# STM32.net
KiCad netlist of a schematic drawn in Altium Designer
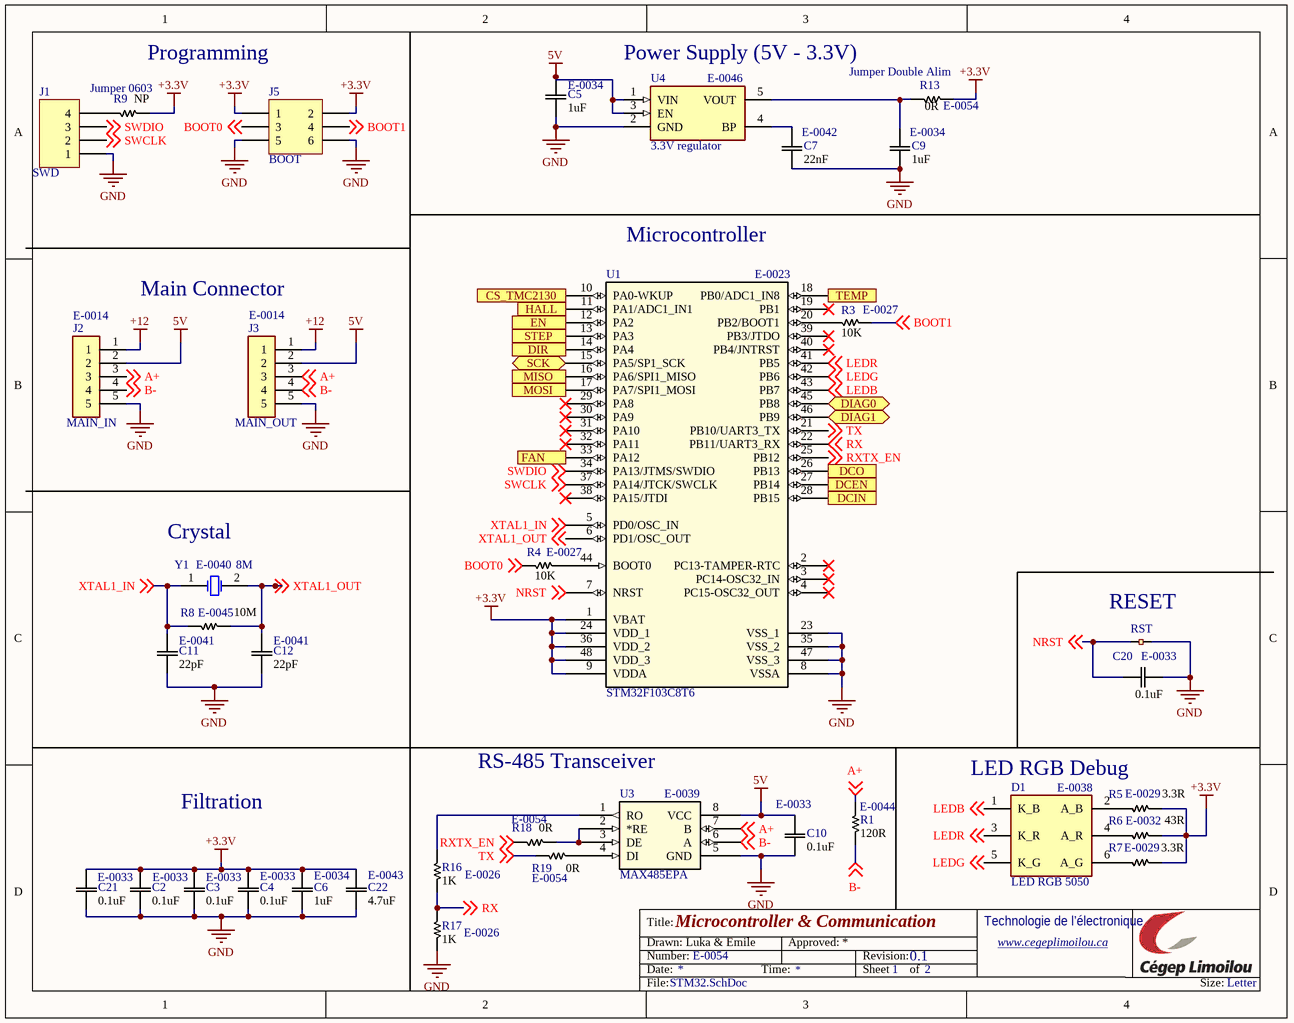
[diagram p0: STM32.SchDoc]

(export (version "E")
  (design (tool "Eeschema 10.0.6"))
  (components
    (comp (ref "C2")
      (value "0.1uF")
      (footprint "0603")
      (description "0.1uF Capacitor 0603 SMD")
      (fields
        (field (name "MANUFACTURER_PART_NUMBER") "C0603C104Z3VACTU")
        (field (name "EXCEL NUMBER") "E-0033")
        (field (name "Comment") "E-0033")
        (field (name "COPYRIGHT") "Luka & Émile")
      )
      (libsource (lib "Motor Driver") (part "E-0033"))
    )
    (comp (ref "C3")
      (value "0.1uF")
      (footprint "0603")
      (description "0.1uF Capacitor 0603 SMD")
      (fields
        (field (name "MANUFACTURER_PART_NUMBER") "C0603C104Z3VACTU")
        (field (name "EXCEL NUMBER") "E-0033")
        (field (name "Comment") "E-0033")
        (field (name "COPYRIGHT") "Luka & Émile")
      )
      (libsource (lib "Motor Driver") (part "E-0033"))
    )
    (comp (ref "C4")
      (value "0.1uF")
      (footprint "0603")
      (description "0.1uF Capacitor 0603 SMD")
      (fields
        (field (name "MANUFACTURER_PART_NUMBER") "C0603C104Z3VACTU")
        (field (name "EXCEL NUMBER") "E-0033")
        (field (name "Comment") "E-0033")
        (field (name "COPYRIGHT") "Luka & Émile")
      )
      (libsource (lib "Motor Driver") (part "E-0033"))
    )
    (comp (ref "C5")
      (value "1uF")
      (footprint "0603")
      (description "1uf Capacitor 0603 SMD")
      (fields
        (field (name "MANUFACTURER_PART_NUMBER") "CL10A105KA8NNNC")
        (field (name "EXCEL NUMBER") "E-0034")
        (field (name "Comment") "E-0034")
        (field (name "COPYRIGHT") "Luka & Émile")
      )
      (libsource (lib "Motor Driver") (part "E-0034"))
    )
    (comp (ref "C6")
      (value "1uF")
      (footprint "0603")
      (description "1uf Capacitor 0603 SMD")
      (fields
        (field (name "MANUFACTURER_PART_NUMBER") "CL10A105KA8NNNC")
        (field (name "EXCEL NUMBER") "E-0034")
        (field (name "Comment") "E-0034")
        (field (name "COPYRIGHT") "Luka & Émile")
      )
      (libsource (lib "Motor Driver") (part "E-0034"))
    )
    (comp (ref "C7")
      (value "22nF")
      (footprint "0603")
      (description "22nF Capacitor 0603 SMD")
      (fields
        (field (name "MANUFACTURER_PART_NUMBER") "C0603C223K1RACTU")
        (field (name "EXCEL NUMBER") "E-0042")
        (field (name "Comment") "E-0042")
        (field (name "COPYRIGHT") "Luka & Émile")
      )
      (libsource (lib "Motor Driver") (part "E-0042"))
    )
    (comp (ref "C9")
      (value "1uF")
      (footprint "0603")
      (description "1uf Capacitor 0603 SMD")
      (fields
        (field (name "MANUFACTURER_PART_NUMBER") "CL10A105KA8NNNC")
        (field (name "EXCEL NUMBER") "E-0034")
        (field (name "Comment") "E-0034")
        (field (name "COPYRIGHT") "Luka & Émile")
      )
      (libsource (lib "Motor Driver") (part "E-0034"))
    )
    (comp (ref "C10")
      (value "0.1uF")
      (footprint "0603")
      (description "0.1uF Capacitor 0603 SMD")
      (fields
        (field (name "MANUFACTURER_PART_NUMBER") "C0603C104Z3VACTU")
        (field (name "EXCEL NUMBER") "E-0033")
        (field (name "Comment") "E-0033")
        (field (name "COPYRIGHT") "Luka & Émile")
      )
      (libsource (lib "Motor Driver") (part "E-0033"))
    )
    (comp (ref "C11")
      (value "22pF")
      (footprint "0603")
      (description "22pF Capacitor 0603 SMD")
      (fields
        (field (name "MANUFACTURER_PART_NUMBER") "C0603C220J1GACTU")
        (field (name "EXCEL NUMBER") "E-0041")
        (field (name "Comment") "E-0041")
        (field (name "COPYRIGHT") "Luka & Émile")
      )
      (libsource (lib "Motor Driver") (part "E-0041"))
    )
    (comp (ref "C12")
      (value "22pF")
      (footprint "0603")
      (description "22pF Capacitor 0603 SMD")
      (fields
        (field (name "MANUFACTURER_PART_NUMBER") "C0603C220J1GACTU")
        (field (name "EXCEL NUMBER") "E-0041")
        (field (name "Comment") "E-0041")
        (field (name "COPYRIGHT") "Luka & Émile")
      )
      (libsource (lib "Motor Driver") (part "E-0041"))
    )
    (comp (ref "C20")
      (value "0.1uF")
      (footprint "0603")
      (description "0.1uF Capacitor 0603 SMD")
      (fields
        (field (name "MANUFACTURER_PART_NUMBER") "C0603C104Z3VACTU")
        (field (name "EXCEL NUMBER") "E-0033")
        (field (name "Comment") "E-0033")
        (field (name "COPYRIGHT") "Luka & Émile")
      )
      (libsource (lib "Motor Driver") (part "E-0033"))
    )
    (comp (ref "C21")
      (value "0.1uF")
      (footprint "0603")
      (description "0.1uF Capacitor 0603 SMD")
      (fields
        (field (name "MANUFACTURER_PART_NUMBER") "C0603C104Z3VACTU")
        (field (name "EXCEL NUMBER") "E-0033")
        (field (name "Comment") "E-0033")
        (field (name "COPYRIGHT") "Luka & Émile")
      )
      (libsource (lib "Motor Driver") (part "E-0033"))
    )
    (comp (ref "C22")
      (value "4.7uF")
      (footprint "0603")
      (description "4.7uF Capacitor 0603 SMD")
      (fields
        (field (name "MANUFACTURER_PART_NUMBER") "C0603C475K9PACTU")
        (field (name "EXCEL NUMBER") "E-0043")
        (field (name "Comment") "E-0043")
        (field (name "COPYRIGHT") "Luka & Émile")
      )
      (libsource (lib "Motor Driver") (part "E-0043"))
    )
    (comp (ref "D1")
      (value "LED RGB 5050")
      (footprint "LED 5050")
      (fields
        (field (name "MANUFACTURER_PART_NUMBER") "150505M173300")
        (field (name "EXCEL NUMBER") "E-0038")
        (field (name "COPYRIGHT") "Luka & Émile")
      )
      (libsource (lib "Motor Driver") (part "E-0038"))
    )
    (comp (ref "J1")
      (value "SWD")
      (footprint "HDR1X4")
      (description "Header, 4POS")
      (fields
        (field (name "MANUFACTURER_PART_NUMBER") "61300411121")
        (field (name "COPYRIGHT") "Luka & Émile")
      )
      (libsource (lib "Motor Driver") (part "E-0048"))
    )
    (comp (ref "J2")
      (value "MAIN_IN")
      (footprint "JST 5POS 2.5mm 90°")
      (description "Connector JST 5POS")
      (fields
        (field (name "MANUFACTURER_PART_NUMBER") "S5B-XH-A-1(LF)(SN)")
        (field (name "EXCEL NUMBER") "E-0014")
        (field (name "COPYRIGHT") "Luka & Émile")
      )
      (libsource (lib "Motor Driver") (part "E-0014"))
    )
    (comp (ref "J3")
      (value "MAIN_OUT")
      (footprint "JST 5POS 2.5mm 90°")
      (description "Connector JST 5POS")
      (fields
        (field (name "MANUFACTURER_PART_NUMBER") "S5B-XH-A-1(LF)(SN)")
        (field (name "EXCEL NUMBER") "E-0014")
        (field (name "COPYRIGHT") "Luka & Émile")
      )
      (libsource (lib "Motor Driver") (part "E-0014"))
    )
    (comp (ref "J5")
      (value "BOOT")
      (footprint "Header 3x2 1.27mm SMD")
      (description "Header, 3-Pin, Dual row")
      (fields
        (field (name "MANUFACTURER_PART_NUMBER") "GRPB032VWVN-RC")
        (field (name "COPYRIGHT") "Luka & Émile")
      )
      (libsource (lib "Motor Driver") (part "E-0049"))
    )
    (comp (ref "R1")
      (value "120R")
      (footprint "0603")
      (description "120R Resistor 0603 SMD")
      (fields
        (field (name "MANUFACTURER_PART_NUMBER") "KDV06FR120ET")
        (field (name "EXCEL NUMBER") "E-0044")
        (field (name "Comment") "E-0044")
        (field (name "COPYRIGHT") "Luka & Émile")
      )
      (libsource (lib "Motor Driver") (part "E-0044"))
    )
    (comp (ref "R3")
      (value "10K")
      (footprint "0603")
      (description "10K Resistor 0603 SMD")
      (fields
        (field (name "MANUFACTURER_PART_NUMBER") "RMCF0603JT10K0")
        (field (name "EXCEL NUMBER") "E-0027")
        (field (name "Comment") "E-0027")
        (field (name "COPYRIGHT") "Luka & Émile")
      )
      (libsource (lib "Motor Driver") (part "E-0027"))
    )
    (comp (ref "R4")
      (value "10K")
      (footprint "0603")
      (description "10K Resistor 0603 SMD")
      (fields
        (field (name "MANUFACTURER_PART_NUMBER") "RMCF0603JT10K0")
        (field (name "EXCEL NUMBER") "E-0027")
        (field (name "Comment") "Resistor 0603")
        (field (name "COPYRIGHT") "Luka & Émile")
      )
      (libsource (lib "Motor Driver") (part "E-0027"))
    )
    (comp (ref "R5")
      (value "3.3R")
      (footprint "0603")
      (description "3.3R Resistor 0603 SMD")
      (fields
        (field (name "MANUFACTURER_PART_NUMBER") "MCR03ERTJ3R3")
        (field (name "EXCEL NUMBER") "E-0029")
        (field (name "Comment") "E-0029")
        (field (name "COPYRIGHT") "Luka & Émile")
      )
      (libsource (lib "Motor Driver") (part "E-0029"))
    )
    (comp (ref "R6")
      (value "43R")
      (footprint "0603")
      (description "43R Resistor 0603 SMD")
      (fields
        (field (name "MANUFACTURER_PART_NUMBER") "RK73B1JTTD430J")
        (field (name "EXCEL NUMBER") "E-0032")
        (field (name "Comment") "E-0032")
        (field (name "COPYRIGHT") "Luka & Émile")
      )
      (libsource (lib "Motor Driver") (part "E-0032"))
    )
    (comp (ref "R7")
      (value "3.3R")
      (footprint "0603")
      (description "3.3R Resistor 0603 SMD")
      (fields
        (field (name "MANUFACTURER_PART_NUMBER") "MCR03ERTJ3R3")
        (field (name "EXCEL NUMBER") "E-0029")
        (field (name "Comment") "E-0029")
        (field (name "COPYRIGHT") "Luka & Émile")
      )
      (libsource (lib "Motor Driver") (part "E-0029"))
    )
    (comp (ref "R8")
      (value "10M")
      (footprint "0603")
      (description "10M Resistor 0603 SMD")
      (fields
        (field (name "MANUFACTURER_PART_NUMBER") "CRCW060310M0FKEAC")
        (field (name "EXCEL NUMBER") "E-0045")
        (field (name "Comment") "E-0045")
        (field (name "COPYRIGHT") "Luka & Émile")
      )
      (libsource (lib "Motor Driver") (part "E-0045"))
    )
    (comp (ref "R9")
      (value "Jumper 0603")
      (footprint "0603")
      (fields (field (name "ALTIUM_VALUE") "NP") (field (name "COPYRIGHT") "Luka & Émile"))
      (libsource (lib "Motor Driver") (part "Jumper"))
    )
    (comp (ref "R13")
      (value "0R")
      (footprint "0603")
      (description "0R Resistor 0603 SMD")
      (fields
        (field (name "EXCEL NUMBER") "E-0054")
        (field (name "Comment") "Resistor 0603")
        (field (name "COPYRIGHT") "Luka & Émile")
      )
      (libsource (lib "Motor Driver") (part "E-0056"))
    )
    (comp (ref "R16")
      (value "1K")
      (footprint "0603")
      (description "1K Resistor 0603 SMD")
      (fields
        (field (name "MANUFACTURER_PART_NUMBER") "RK73B1JTTD102J")
        (field (name "EXCEL NUMBER") "E-0026")
        (field (name "Comment") "E-0026")
        (field (name "COPYRIGHT") "Luka & Émile")
      )
      (libsource (lib "Motor Driver") (part "E-0026"))
    )
    (comp (ref "R17")
      (value "1K")
      (footprint "0603")
      (description "1K Resistor 0603 SMD")
      (fields
        (field (name "MANUFACTURER_PART_NUMBER") "RK73B1JTTD102J")
        (field (name "EXCEL NUMBER") "E-0026")
        (field (name "Comment") "E-0026")
        (field (name "COPYRIGHT") "Luka & Émile")
      )
      (libsource (lib "Motor Driver") (part "E-0026"))
    )
    (comp (ref "R18")
      (value "0R")
      (footprint "0603")
      (description "0R Resistor 0603 SMD")
      (fields
        (field (name "EXCEL NUMBER") "E-0054")
        (field (name "Comment") "Resistor 0603")
        (field (name "COPYRIGHT") "Luka & Émile")
      )
      (libsource (lib "Motor Driver") (part "E-0056"))
    )
    (comp (ref "R19")
      (value "0R")
      (footprint "0603")
      (description "0R Resistor 0603 SMD")
      (fields
        (field (name "EXCEL NUMBER") "E-0054")
        (field (name "Comment") "Resistor 0603")
        (field (name "COPYRIGHT") "Luka & Émile")
      )
      (libsource (lib "Motor Driver") (part "E-0056"))
    )
    (comp (ref "RST")
      (value "~")
      (footprint "PAD")
      (description "SMD Pad for contact")
      (fields (field (name "COPYRIGHT") "Luka & Émile"))
      (libsource (lib "Motor Driver") (part "PAD"))
    )
    (comp (ref "U1")
      (value "STM32F103C8T6")
      (footprint "LQFP-48")
      (description "STM32F103C8T6 Bluepill")
      (fields
        (field (name "MANUFACTURER_PART_NUMBER") "STM32F103C8T6TR")
        (field (name "EXCEL NUMBER") "E-0023")
        (field (name "COPYRIGHT") "Luka & Émile")
      )
      (libsource (lib "Motor Driver") (part "E-0023"))
    )
    (comp (ref "U3")
      (value "MAX485EPA")
      (footprint "DIP 8 - 3D")
      (description "RS485 Communication")
      (fields
        (field (name "MANUFACTURER_PART_NUMBER") "MAX485CPA+")
        (field (name "EXCEL NUMBER") "E-0039")
        (field (name "COPYRIGHT") "Luka & Émile")
      )
      (libsource (lib "Motor Driver") (part "E-0039"))
    )
    (comp (ref "U4")
      (value "3.3V regulator")
      (footprint "SamacSys:SOT94P279X130-5N")
      (description "Voltage Regulator 3.3V SOT-23-5")
      (fields
        (field (name "MANUFACTURER_PART_NUMBER") "RT9193-28GB")
        (field (name "EXCEL NUMBER") "E-0046")
        (field (name "COPYRIGHT") "Luka & Émile")
      )
      (libsource (lib "Motor Driver") (part "E-0046"))
    )
    (comp (ref "Y1")
      (value "8M")
      (footprint "ATS080B-E")
      (description "Crystal 8M")
      (fields
        (field (name "MANUFACTURER_PART_NUMBER") "ATS080B-E")
        (field (name "EXCEL NUMBER") "E-0040")
        (field (name "COPYRIGHT") "Luka & Émile")
      )
      (libsource (lib "Motor Driver") (part "E-0040"))
    )
  )
  (nets
    (net (code "1") (name "+3.3V") (class "Default")
      (node (ref "C2") (pin "2") (pinfunction "2_2") (pintype "passive"))
      (node (ref "C21") (pin "2") (pinfunction "2_2") (pintype "passive"))
      (node (ref "C22") (pin "2") (pinfunction "2_2") (pintype "passive"))
      (node (ref "C3") (pin "2") (pinfunction "2_2") (pintype "passive"))
      (node (ref "C4") (pin "2") (pinfunction "2_2") (pintype "passive"))
      (node (ref "C6") (pin "2") (pinfunction "2_2") (pintype "passive"))
      (node (ref "J5") (pin "1") (pinfunction "1_1") (pintype "passive"))
      (node (ref "J5") (pin "2") (pinfunction "2_2") (pintype "passive"))
      (node (ref "R13") (pin "2") (pinfunction "2_2") (pintype "passive"))
      (node (ref "R5") (pin "2") (pinfunction "2_2") (pintype "passive"))
      (node (ref "R6") (pin "2") (pinfunction "2_2") (pintype "passive"))
      (node (ref "R7") (pin "2") (pinfunction "2_2") (pintype "passive"))
      (node (ref "R9") (pin "2") (pinfunction "2_2") (pintype "passive"))
      (node (ref "U1") (pin "1") (pinfunction "VBAT_1") (pintype "power_in"))
      (node (ref "U1") (pin "24") (pinfunction "VDD_1_24") (pintype "power_in"))
      (node (ref "U1") (pin "36") (pinfunction "VDD_2_36") (pintype "power_in"))
      (node (ref "U1") (pin "48") (pinfunction "VDD_3_48") (pintype "power_in"))
      (node (ref "U1") (pin "9") (pinfunction "VDDA_9") (pintype "power_in"))
    )
    (net (code "2") (name "+12") (class "Default")
      (node (ref "J2") (pin "1") (pinfunction "1_1") (pintype "passive"))
      (node (ref "J3") (pin "1") (pinfunction "1_1") (pintype "passive"))
    )
    (net (code "3") (name "/CS_TMC2130") (class "Default")
      (node (ref "U1") (pin "10") (pinfunction "PA0-WKUP_10") (pintype "bidirectional"))
    )
    (net (code "4") (name "/DCEN") (class "Default")
      (node (ref "U1") (pin "27") (pinfunction "PB14_27") (pintype "bidirectional"))
    )
    (net (code "5") (name "/DCIN") (class "Default")
      (node (ref "U1") (pin "28") (pinfunction "PB15_28") (pintype "bidirectional"))
    )
    (net (code "6") (name "/DCO") (class "Default")
      (node (ref "U1") (pin "26") (pinfunction "PB13_26") (pintype "bidirectional"))
    )
    (net (code "7") (name "/DIAG0") (class "Default")
      (node (ref "U1") (pin "45") (pinfunction "PB8_45") (pintype "bidirectional"))
    )
    (net (code "8") (name "/DIAG1") (class "Default")
      (node (ref "U1") (pin "46") (pinfunction "PB9_46") (pintype "bidirectional"))
    )
    (net (code "9") (name "/DIR") (class "Default")
      (node (ref "U1") (pin "14") (pinfunction "PA4_14") (pintype "bidirectional"))
    )
    (net (code "10") (name "/EN") (class "Default")
      (node (ref "U1") (pin "12") (pinfunction "PA2_12") (pintype "bidirectional"))
    )
    (net (code "11") (name "/FAN") (class "Default")
      (node (ref "U1") (pin "33") (pinfunction "PA12_33") (pintype "bidirectional"))
    )
    (net (code "12") (name "/HALL") (class "Default")
      (node (ref "U1") (pin "11") (pinfunction "PA1/ADC1_IN1_11") (pintype "bidirectional"))
    )
    (net (code "13") (name "/MISO") (class "Default")
      (node (ref "U1") (pin "16") (pinfunction "PA6/SPI1_MISO_16") (pintype "bidirectional"))
    )
    (net (code "14") (name "/MOSI") (class "Default")
      (node (ref "U1") (pin "17") (pinfunction "PA7/SPI1_MOSI_17") (pintype "bidirectional"))
    )
    (net (code "15") (name "/SCK") (class "Default")
      (node (ref "U1") (pin "15") (pinfunction "PA5/SP1_SCK_15") (pintype "bidirectional"))
    )
    (net (code "16") (name "/STEP") (class "Default")
      (node (ref "U1") (pin "13") (pinfunction "PA3_13") (pintype "bidirectional"))
    )
    (net (code "17") (name "/TEMP") (class "Default")
      (node (ref "U1") (pin "18") (pinfunction "PB0/ADC1_IN8_18") (pintype "bidirectional"))
    )
    (net (code "18") (name "5V") (class "Default")
      (node (ref "C10") (pin "2") (pinfunction "2_2") (pintype "passive"))
      (node (ref "C5") (pin "2") (pinfunction "2_2") (pintype "passive"))
      (node (ref "J2") (pin "2") (pinfunction "2_2") (pintype "passive"))
      (node (ref "J3") (pin "2") (pinfunction "2_2") (pintype "passive"))
      (node (ref "U3") (pin "8") (pinfunction "VCC_8") (pintype "power_in"))
      (node (ref "U4") (pin "1") (pinfunction "VIN_1") (pintype "input"))
      (node (ref "U4") (pin "3") (pinfunction "EN_3") (pintype "input"))
    )
    (net (code "19") (name "A+") (class "Default")
      (node (ref "J2") (pin "3") (pinfunction "3_3") (pintype "passive"))
      (node (ref "J3") (pin "3") (pinfunction "3_3") (pintype "passive"))
      (node (ref "R1") (pin "2") (pinfunction "2_2") (pintype "passive"))
      (node (ref "U3") (pin "7") (pinfunction "B_7") (pintype "bidirectional"))
    )
    (net (code "20") (name "B-") (class "Default")
      (node (ref "J2") (pin "4") (pinfunction "4_4") (pintype "passive"))
      (node (ref "J3") (pin "4") (pinfunction "4_4") (pintype "passive"))
      (node (ref "R1") (pin "1") (pinfunction "1_1") (pintype "passive"))
      (node (ref "U3") (pin "6") (pinfunction "A_6") (pintype "bidirectional"))
    )
    (net (code "21") (name "BOOT0") (class "Default")
      (node (ref "J5") (pin "3") (pinfunction "3_3") (pintype "passive"))
      (node (ref "R4") (pin "1") (pinfunction "1_1") (pintype "passive"))
    )
    (net (code "22") (name "BOOT1") (class "Default")
      (node (ref "J5") (pin "4") (pinfunction "4_4") (pintype "passive"))
      (node (ref "R3") (pin "2") (pinfunction "2_2") (pintype "passive"))
    )
    (net (code "23") (name "GND") (class "Default")
      (node (ref "C10") (pin "1") (pinfunction "1_1") (pintype "passive"))
      (node (ref "C11") (pin "1") (pinfunction "1_1") (pintype "passive"))
      (node (ref "C12") (pin "1") (pinfunction "1_1") (pintype "passive"))
      (node (ref "C2") (pin "1") (pinfunction "1_1") (pintype "passive"))
      (node (ref "C20") (pin "1") (pinfunction "1_1") (pintype "passive"))
      (node (ref "C21") (pin "1") (pinfunction "1_1") (pintype "passive"))
      (node (ref "C22") (pin "1") (pinfunction "1_1") (pintype "passive"))
      (node (ref "C3") (pin "1") (pinfunction "1_1") (pintype "passive"))
      (node (ref "C4") (pin "1") (pinfunction "1_1") (pintype "passive"))
      (node (ref "C5") (pin "1") (pinfunction "1_1") (pintype "passive"))
      (node (ref "C6") (pin "1") (pinfunction "1_1") (pintype "passive"))
      (node (ref "C7") (pin "1") (pinfunction "1_1") (pintype "passive"))
      (node (ref "C9") (pin "1") (pinfunction "1_1") (pintype "passive"))
      (node (ref "J1") (pin "1") (pinfunction "1_1") (pintype "passive"))
      (node (ref "J2") (pin "5") (pinfunction "5_5") (pintype "passive"))
      (node (ref "J3") (pin "5") (pinfunction "5_5") (pintype "passive"))
      (node (ref "J5") (pin "5") (pinfunction "5_5") (pintype "passive"))
      (node (ref "J5") (pin "6") (pinfunction "6_6") (pintype "passive"))
      (node (ref "R17") (pin "2") (pinfunction "2_2") (pintype "passive"))
      (node (ref "RST") (pin "1") (pinfunction "1_1") (pintype "passive"))
      (node (ref "U1") (pin "23") (pinfunction "VSS_1_23") (pintype "power_in"))
      (node (ref "U1") (pin "35") (pinfunction "VSS_2_35") (pintype "power_in"))
      (node (ref "U1") (pin "47") (pinfunction "VSS_3_47") (pintype "power_in"))
      (node (ref "U1") (pin "8") (pinfunction "VSSA_8") (pintype "power_in"))
      (node (ref "U3") (pin "5") (pinfunction "GND_5") (pintype "power_in"))
      (node (ref "U4") (pin "2") (pinfunction "GND_2") (pintype "power_in"))
    )
    (net (code "24") (name "LEDB") (class "Default")
      (node (ref "D1") (pin "1") (pinfunction "K_B_1") (pintype "passive"))
      (node (ref "U1") (pin "43") (pinfunction "PB7_43") (pintype "bidirectional"))
    )
    (net (code "25") (name "LEDG") (class "Default")
      (node (ref "D1") (pin "5") (pinfunction "K_G_5") (pintype "passive"))
      (node (ref "U1") (pin "42") (pinfunction "PB6_42") (pintype "bidirectional"))
    )
    (net (code "26") (name "LEDR") (class "Default")
      (node (ref "D1") (pin "3") (pinfunction "K_R_3") (pintype "passive"))
      (node (ref "U1") (pin "41") (pinfunction "PB5_41") (pintype "bidirectional"))
    )
    (net (code "27") (name "NRST") (class "Default")
      (node (ref "C20") (pin "2") (pinfunction "2_2") (pintype "passive"))
      (node (ref "RST") (pin "2") (pinfunction "2_2") (pintype "passive"))
      (node (ref "U1") (pin "7") (pinfunction "NRST_7") (pintype "bidirectional"))
    )
    (net (code "28") (name "Net-(D1-A_B)") (class "Default")
      (node (ref "D1") (pin "2") (pinfunction "A_B_2") (pintype "passive"))
      (node (ref "R5") (pin "1") (pinfunction "1_1") (pintype "passive"))
    )
    (net (code "29") (name "Net-(D1-A_G)") (class "Default")
      (node (ref "D1") (pin "6") (pinfunction "A_G_6") (pintype "passive"))
      (node (ref "R7") (pin "1") (pinfunction "1_1") (pintype "passive"))
    )
    (net (code "30") (name "Net-(D1-A_R)") (class "Default")
      (node (ref "D1") (pin "4") (pinfunction "A_R_4") (pintype "passive"))
      (node (ref "R6") (pin "1") (pinfunction "1_1") (pintype "passive"))
    )
    (net (code "31") (name "Net-(J1-Pad4)") (class "Default")
      (node (ref "J1") (pin "4") (pinfunction "4_4") (pintype "passive"))
      (node (ref "R9") (pin "1") (pinfunction "1_1") (pintype "passive"))
    )
    (net (code "32") (name "Net-(U1-BOOT0)") (class "Default")
      (node (ref "R4") (pin "2") (pinfunction "2_2") (pintype "passive"))
      (node (ref "U1") (pin "44") (pinfunction "BOOT0_44") (pintype "input"))
    )
    (net (code "33") (name "Net-(U1-PB2{slash}BOOT1)") (class "Default")
      (node (ref "R3") (pin "1") (pinfunction "1_1") (pintype "passive"))
      (node (ref "U1") (pin "20") (pinfunction "PB2/BOOT1_20") (pintype "bidirectional"))
    )
    (net (code "34") (name "Net-(U3-*RE)") (class "Default")
      (node (ref "R18") (pin "2") (pinfunction "2_2") (pintype "passive"))
      (node (ref "U3") (pin "2") (pinfunction "*RE_2") (pintype "input"))
      (node (ref "U3") (pin "3") (pinfunction "DE_3") (pintype "input"))
    )
    (net (code "35") (name "Net-(U3-DI)") (class "Default")
      (node (ref "R19") (pin "2") (pinfunction "2_2") (pintype "passive"))
      (node (ref "U3") (pin "4") (pinfunction "DI_4") (pintype "input"))
    )
    (net (code "36") (name "Net-(U3-RO)") (class "Default")
      (node (ref "R16") (pin "1") (pinfunction "1_1") (pintype "passive"))
      (node (ref "U3") (pin "1") (pinfunction "RO_1") (pintype "output"))
    )
    (net (code "37") (name "Net-(U4-BP)") (class "Default")
      (node (ref "C7") (pin "2") (pinfunction "2_2") (pintype "passive"))
      (node (ref "U4") (pin "4") (pinfunction "BP_4") (pintype "passive"))
    )
    (net (code "38") (name "Net-(U4-VOUT)") (class "Default")
      (node (ref "C9") (pin "2") (pinfunction "2_2") (pintype "passive"))
      (node (ref "R13") (pin "1") (pinfunction "1_1") (pintype "passive"))
      (node (ref "U4") (pin "5") (pinfunction "VOUT_5") (pintype "passive"))
    )
    (net (code "39") (name "RX") (class "Default")
      (node (ref "R16") (pin "2") (pinfunction "2_2") (pintype "passive"))
      (node (ref "R17") (pin "1") (pinfunction "1_1") (pintype "passive"))
      (node (ref "U1") (pin "22") (pinfunction "PB11/UART3_RX_22") (pintype "bidirectional"))
    )
    (net (code "40") (name "RXTX_EN") (class "Default")
      (node (ref "R18") (pin "1") (pinfunction "1_1") (pintype "passive"))
      (node (ref "U1") (pin "25") (pinfunction "PB12_25") (pintype "bidirectional"))
    )
    (net (code "41") (name "SWCLK") (class "Default")
      (node (ref "J1") (pin "2") (pinfunction "2_2") (pintype "passive"))
      (node (ref "U1") (pin "37") (pinfunction "PA14/JTCK/SWCLK_37") (pintype "bidirectional"))
    )
    (net (code "42") (name "SWDIO") (class "Default")
      (node (ref "J1") (pin "3") (pinfunction "3_3") (pintype "passive"))
      (node (ref "U1") (pin "34") (pinfunction "PA13/JTMS/SWDIO_34") (pintype "bidirectional"))
    )
    (net (code "43") (name "TX") (class "Default")
      (node (ref "R19") (pin "1") (pinfunction "1_1") (pintype "passive"))
      (node (ref "U1") (pin "21") (pinfunction "PB10/UART3_TX_21") (pintype "bidirectional"))
    )
    (net (code "44") (name "XTAL1_IN") (class "Default")
      (node (ref "C11") (pin "2") (pinfunction "2_2") (pintype "passive"))
      (node (ref "R8") (pin "1") (pinfunction "1_1") (pintype "passive"))
      (node (ref "U1") (pin "5") (pinfunction "PD0/OSC_IN_5") (pintype "bidirectional"))
      (node (ref "Y1") (pin "1") (pinfunction "OSC1_1") (pintype "passive"))
    )
    (net (code "45") (name "XTAL1_OUT") (class "Default")
      (node (ref "C12") (pin "2") (pinfunction "2_2") (pintype "passive"))
      (node (ref "R8") (pin "2") (pinfunction "2_2") (pintype "passive"))
      (node (ref "U1") (pin "6") (pinfunction "PD1/OSC_OUT_6") (pintype "bidirectional"))
      (node (ref "Y1") (pin "2") (pinfunction "OSC2_2") (pintype "passive"))
    )
    (net (code "46") (name "unconnected-(U1-PA8-Pad29)") (class "Default")
      (node (ref "U1") (pin "29") (pinfunction "PA8_29") (pintype "bidirectional+no_connect"))
    )
    (net (code "47") (name "unconnected-(U1-PA9-Pad30)") (class "Default")
      (node (ref "U1") (pin "30") (pinfunction "PA9_30") (pintype "bidirectional+no_connect"))
    )
    (net (code "48") (name "unconnected-(U1-PA10-Pad31)") (class "Default")
      (node (ref "U1") (pin "31") (pinfunction "PA10_31") (pintype "bidirectional+no_connect"))
    )
    (net (code "49") (name "unconnected-(U1-PA11-Pad32)") (class "Default")
      (node (ref "U1") (pin "32") (pinfunction "PA11_32") (pintype "bidirectional+no_connect"))
    )
    (net (code "50") (name "unconnected-(U1-PA15{slash}JTDI-Pad38)") (class "Default")
      (node (ref "U1") (pin "38") (pinfunction "PA15/JTDI_38") (pintype "bidirectional+no_connect"))
    )
    (net (code "51") (name "unconnected-(U1-PB1-Pad19)") (class "Default")
      (node (ref "U1") (pin "19") (pinfunction "PB1_19") (pintype "bidirectional+no_connect"))
    )
    (net (code "52") (name "unconnected-(U1-PB3{slash}JTDO-Pad39)") (class "Default")
      (node (ref "U1") (pin "39") (pinfunction "PB3/JTDO_39") (pintype "bidirectional+no_connect"))
    )
    (net (code "53") (name "unconnected-(U1-PB4{slash}JNTRST-Pad40)") (class "Default")
      (node (ref "U1") (pin "40") (pinfunction "PB4/JNTRST_40") (pintype "bidirectional+no_connect"))
    )
    (net (code "54") (name "unconnected-(U1-PC13-TAMPER-RTC-Pad2)") (class "Default")
      (node (ref "U1") (pin "2") (pinfunction "PC13-TAMPER-RTC_2") (pintype "bidirectional+no_connect"))
    )
    (net (code "55") (name "unconnected-(U1-PC14-OSC32_IN-Pad3)") (class "Default")
      (node (ref "U1") (pin "3") (pinfunction "PC14-OSC32_IN_3") (pintype "bidirectional+no_connect"))
    )
    (net (code "56") (name "unconnected-(U1-PC15-OSC32_OUT-Pad4)") (class "Default")
      (node (ref "U1") (pin "4") (pinfunction "PC15-OSC32_OUT_4") (pintype "bidirectional+no_connect"))
    )
  )
)
